# LipSync_Main_Board.net
KiCad netlist of a schematic drawn in EAGLE
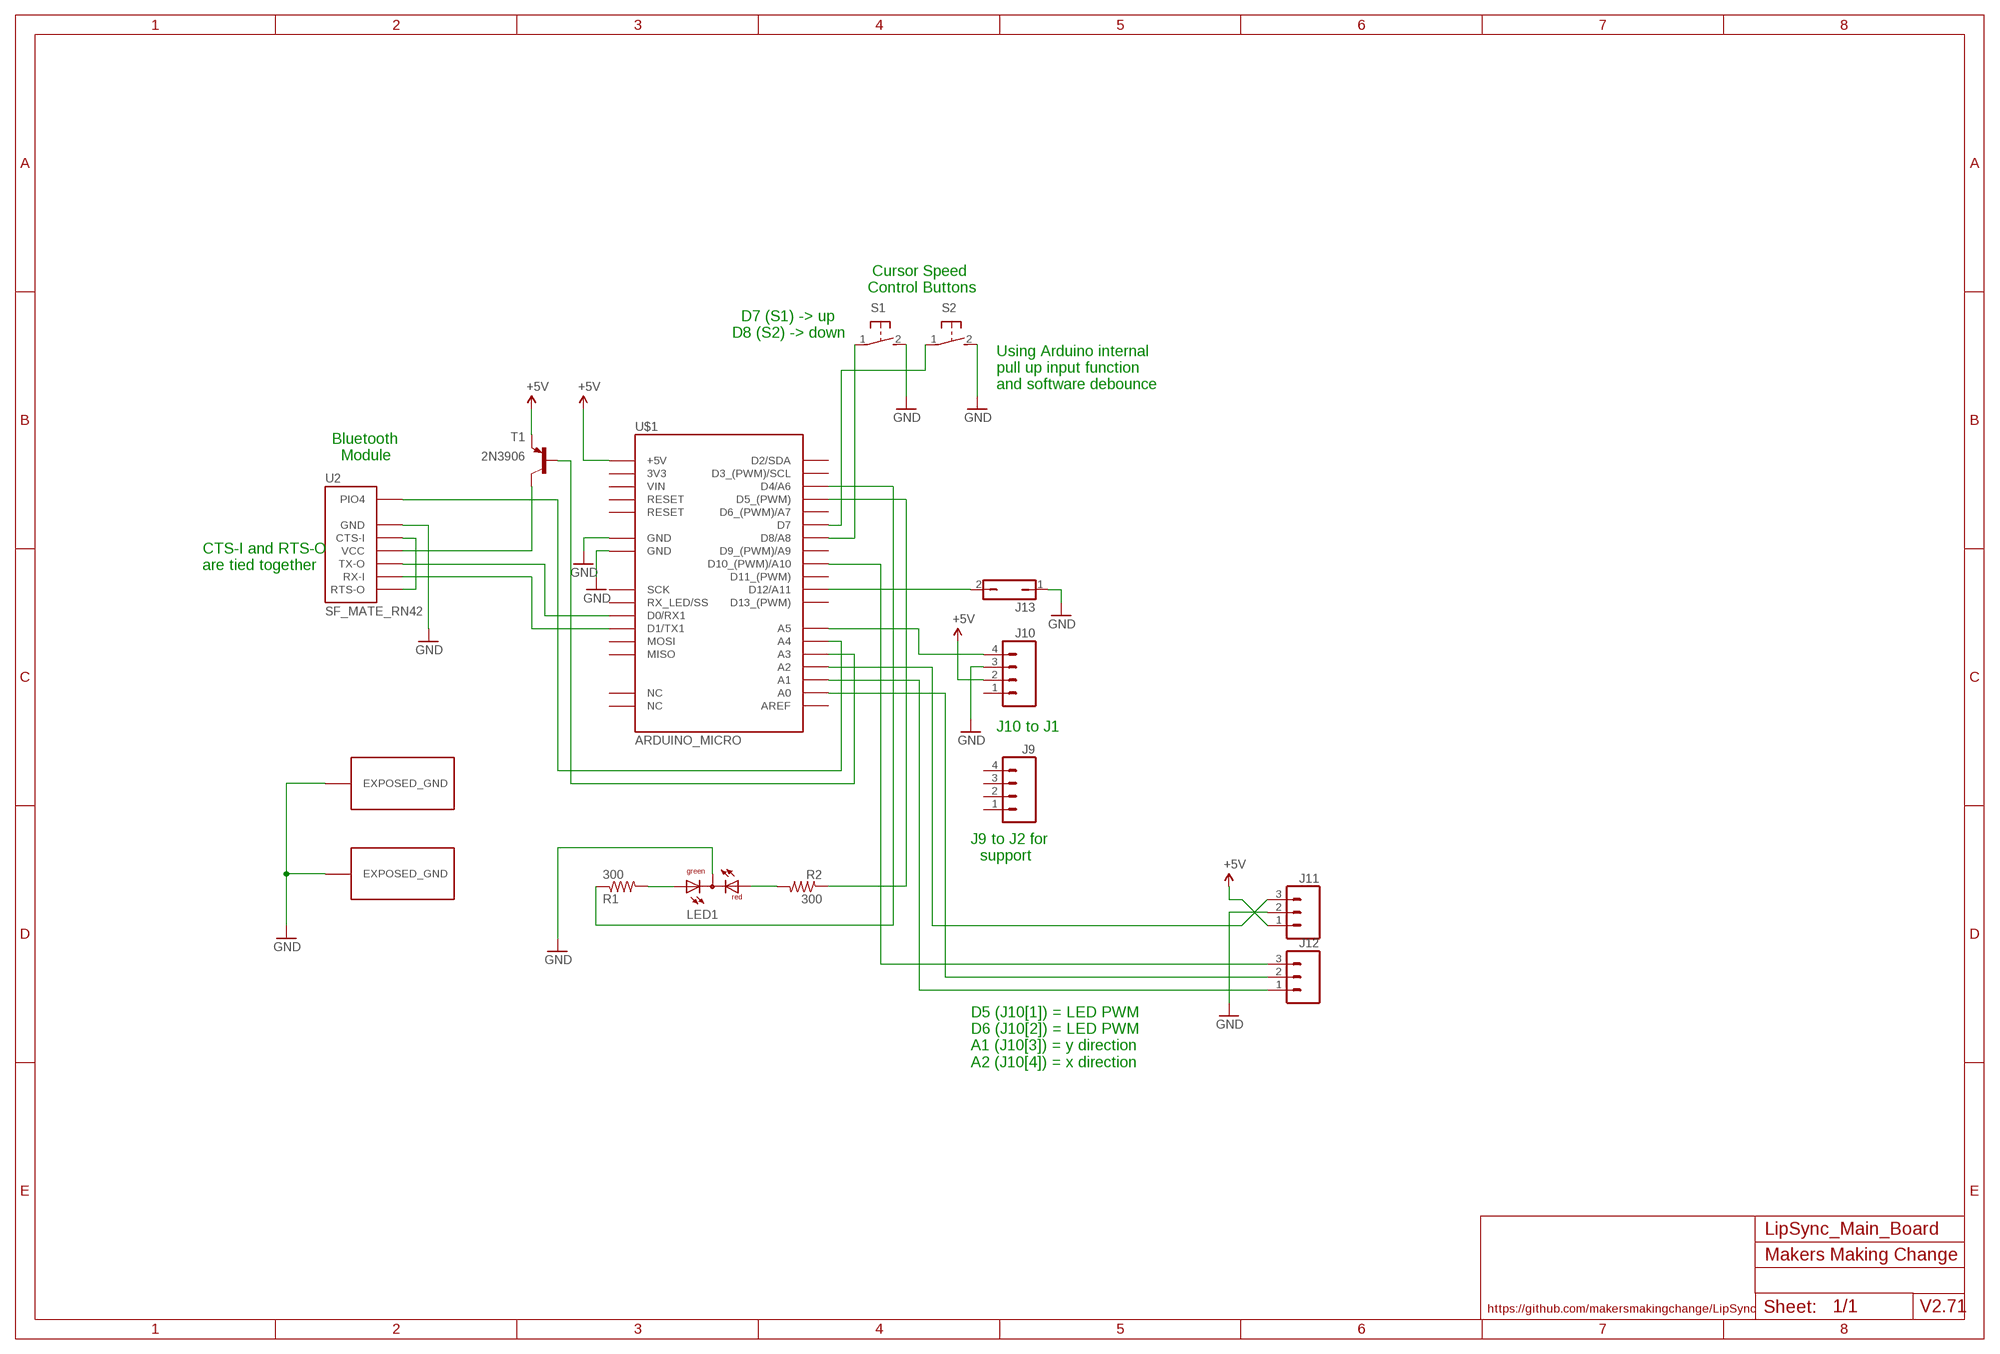
[diagram p0: schematic, sheet 1]

(export (version "E")
  (design (tool "Eeschema 10.0.6"))
  (components
    (comp (ref "J9")
      (value "M04PTH")
      (footprint "eagle-import:1X04")
      (libsource (lib "eagle-import") (part "M04PTH"))
    )
    (comp (ref "J10")
      (value "M04PTH")
      (footprint "eagle-import:1X04")
      (libsource (lib "eagle-import") (part "M04PTH"))
    )
    (comp (ref "J11")
      (value "M03LOCK")
      (footprint "eagle-import:1X03_LOCK")
      (libsource (lib "eagle-import") (part "M03LOCK"))
    )
    (comp (ref "J12")
      (value "M03LOCK")
      (footprint "eagle-import:1X03_LOCK")
      (libsource (lib "eagle-import") (part "M03LOCK"))
    )
    (comp (ref "J13")
      (value "JP1Q")
      (footprint "eagle-import:JP1")
      (libsource (lib "eagle-import") (part "JP1Q"))
    )
    (comp (ref "LED1")
      (value "DUOLED-RG-C")
      (footprint "eagle-import:DUOLED-C-5MM")
      (libsource (lib "eagle-import") (part "DUOLED-RG-C"))
    )
    (comp (ref "R1")
      (value "300")
      (footprint "eagle-import:AXIAL-0.3")
      (libsource (lib "eagle-import") (part "RESISTORAXIAL-0.3"))
    )
    (comp (ref "R2")
      (value "300")
      (footprint "eagle-import:AXIAL-0.3")
      (libsource (lib "eagle-import") (part "RESISTORAXIAL-0.3"))
    )
    (comp (ref "S1")
      (value "31-XXB3F-31XX-CUSTOM")
      (footprint "eagle-import:B3F-31XX-CUSTOM")
      (libsource (lib "eagle-import") (part "31-XXB3F-31XX-CUSTOM"))
    )
    (comp (ref "S2")
      (value "31-XXB3F-31XX-CUSTOM")
      (footprint "eagle-import:B3F-31XX-CUSTOM")
      (libsource (lib "eagle-import") (part "31-XXB3F-31XX-CUSTOM"))
    )
    (comp (ref "T1")
      (value "2N3906")
      (footprint "eagle-import:TO92-EBC")
      (libsource (lib "eagle-import") (part "-PNP-TO92-EBC2N3906"))
    )
    (comp (ref "U$1")
      (value "ARDUINO_MICRO")
      (footprint "eagle-import:ARDUINO_MICRO_HEADER_FOOTPRINT")
      (libsource (lib "eagle-import") (part "ARDUINO_MICRO"))
    )
    (comp (ref "U$2")
      (value "EXPOSED_GND")
      (footprint "eagle-import:EXPOSED_GND")
      (libsource (lib "eagle-import") (part "EXPOSED_GND"))
    )
    (comp (ref "U$3")
      (value "EXPOSED_GND")
      (footprint "eagle-import:EXPOSED_GND")
      (libsource (lib "eagle-import") (part "EXPOSED_GND"))
    )
    (comp (ref "U2")
      (value "SF_MATE_RN42")
      (footprint "eagle-import:BLUE_MATE_RN42_HEADER_FOOTPRINT")
      (libsource (lib "eagle-import") (part "SF_MATE_RN42"))
    )
  )
  (nets
    (net (code "1") (name "+5V") (class "Default")
      (node (ref "J10") (pin "2") (pinfunction "2_2") (pintype "passive"))
      (node (ref "J11") (pin "1") (pinfunction "1_1") (pintype "passive"))
      (node (ref "T1") (pin "E") (pinfunction "E_E") (pintype "passive"))
      (node (ref "U$1") (pin "5V") (pinfunction "+5V_5V") (pintype "power_in"))
    )
    (net (code "2") (name "/3V3") (class "Default")
      (node (ref "U$1") (pin "3V3") (pinfunction "3V3_3V3") (pintype "power_in"))
    )
    (net (code "3") (name "EXPOSED_GND") (class "Default")
      (node (ref "J10") (pin "3") (pinfunction "3_3") (pintype "passive"))
      (node (ref "J11") (pin "2") (pinfunction "2_2") (pintype "passive"))
      (node (ref "J13") (pin "1") (pinfunction "1_1") (pintype "passive"))
      (node (ref "LED1") (pin "C") (pinfunction "C_C") (pintype "passive"))
      (node (ref "S1") (pin "2") (pinfunction "S_2") (pintype "passive"))
      (node (ref "S2") (pin "2") (pinfunction "S_2") (pintype "passive"))
      (node (ref "U$1") (pin "GND") (pinfunction "GND_GND") (pintype "power_in"))
      (node (ref "U$1") (pin "GND@1") (pinfunction "GND_GND@1") (pintype "power_in"))
      (node (ref "U$2") (pin "GND1") (pinfunction "EXPOSED_GND_GND1") (pintype "power_in"))
      (node (ref "U$3") (pin "GND1") (pinfunction "EXPOSED_GND_GND1") (pintype "power_in"))
      (node (ref "U2") (pin "GND") (pinfunction "GND_GND") (pintype "power_in"))
    )
    (net (code "4") (name "Net-(J10-Pad4)") (class "Default")
      (node (ref "J10") (pin "4") (pinfunction "4_4") (pintype "passive"))
      (node (ref "U$1") (pin "A5") (pinfunction "A5_A5") (pintype "bidirectional"))
    )
    (net (code "5") (name "Net-(J11-Pad3)") (class "Default")
      (node (ref "J11") (pin "3") (pinfunction "3_3") (pintype "passive"))
      (node (ref "U$1") (pin "A2") (pinfunction "A2_A2") (pintype "bidirectional"))
    )
    (net (code "6") (name "Net-(J12-Pad1)") (class "Default")
      (node (ref "J12") (pin "1") (pinfunction "1_1") (pintype "passive"))
      (node (ref "U$1") (pin "A1") (pinfunction "A1_A1") (pintype "bidirectional"))
    )
    (net (code "7") (name "Net-(J12-Pad2)") (class "Default")
      (node (ref "J12") (pin "2") (pinfunction "2_2") (pintype "passive"))
      (node (ref "U$1") (pin "A0") (pinfunction "A0_A0") (pintype "bidirectional"))
    )
    (net (code "8") (name "Net-(LED1-AG)") (class "Default")
      (node (ref "LED1") (pin "AX") (pinfunction "AG_AX") (pintype "passive"))
      (node (ref "R1") (pin "P$2") (pinfunction "2_P$2") (pintype "passive"))
    )
    (net (code "9") (name "Net-(R1-1)") (class "Default")
      (node (ref "R1") (pin "P$1") (pinfunction "1_P$1") (pintype "passive"))
      (node (ref "U$1") (pin "D4") (pinfunction "D4/A6_D4") (pintype "bidirectional"))
    )
    (net (code "10") (name "Net-(R2-1)") (class "Default")
      (node (ref "R2") (pin "P$1") (pinfunction "1_P$1") (pintype "passive"))
      (node (ref "U$1") (pin "D5") (pinfunction "D5_(PWM)_D5") (pintype "bidirectional"))
    )
    (net (code "11") (name "Net-(R2-2)") (class "Default")
      (node (ref "LED1") (pin "AR") (pinfunction "AR_AR") (pintype "passive"))
      (node (ref "R2") (pin "P$2") (pinfunction "2_P$2") (pintype "passive"))
    )
    (net (code "12") (name "Net-(S1-P)") (class "Default")
      (node (ref "S1") (pin "1") (pinfunction "P_1") (pintype "passive"))
      (node (ref "U$1") (pin "D8") (pinfunction "D8/A8_D8") (pintype "bidirectional"))
    )
    (net (code "13") (name "Net-(S2-P)") (class "Default")
      (node (ref "S2") (pin "1") (pinfunction "P_1") (pintype "passive"))
      (node (ref "U$1") (pin "D7") (pinfunction "D7_D7") (pintype "bidirectional"))
    )
    (net (code "14") (name "Net-(T1-PadB)") (class "Default")
      (node (ref "T1") (pin "B") (pinfunction "B_B") (pintype "passive"))
      (node (ref "U$1") (pin "A3") (pinfunction "A3_A3") (pintype "bidirectional"))
    )
    (net (code "15") (name "Net-(T1-PadC)") (class "Default")
      (node (ref "T1") (pin "C") (pinfunction "C_C") (pintype "passive"))
      (node (ref "U2") (pin "VCC") (pinfunction "VCC_VCC") (pintype "power_in"))
    )
    (net (code "16") (name "Net-(U$1-D0{slash}RX1)") (class "Default")
      (node (ref "U$1") (pin "RX1") (pinfunction "D0/RX1_RX1") (pintype "input"))
      (node (ref "U2") (pin "TX-O") (pinfunction "TX-O_TX-O") (pintype "output"))
    )
    (net (code "17") (name "Net-(U$1-D1{slash}TX1)") (class "Default")
      (node (ref "U$1") (pin "TX1") (pinfunction "D1/TX1_TX1") (pintype "output"))
      (node (ref "U2") (pin "RX-I") (pinfunction "RX-I_RX-I") (pintype "input"))
    )
    (net (code "18") (name "Net-(U$1-D10_(PWM){slash}A10)") (class "Default")
      (node (ref "J12") (pin "3") (pinfunction "3_3") (pintype "passive"))
      (node (ref "U$1") (pin "D10") (pinfunction "D10_(PWM)/A10_D10") (pintype "bidirectional"))
    )
    (net (code "19") (name "Net-(U$1-D12{slash}A11)") (class "Default")
      (node (ref "J13") (pin "2") (pinfunction "2_2") (pintype "passive"))
      (node (ref "U$1") (pin "D12") (pinfunction "D12/A11_D12") (pintype "bidirectional"))
    )
    (net (code "20") (name "Net-(U$1-PadA4)") (class "Default")
      (node (ref "U$1") (pin "A4") (pinfunction "A4_A4") (pintype "bidirectional"))
      (node (ref "U2") (pin "PIO4") (pinfunction "PIO4_PIO4") (pintype "input"))
    )
    (net (code "21") (name "Net-(U2-PadCTS-I)") (class "Default")
      (node (ref "U2") (pin "CTS-I") (pinfunction "CTS-I_CTS-I") (pintype "input"))
      (node (ref "U2") (pin "RTS-O") (pinfunction "RTS-O_RTS-O") (pintype "output"))
    )
    (net (code "22") (name "unconnected-(J9-Pad1)") (class "Default")
      (node (ref "J9") (pin "1") (pinfunction "1_1") (pintype "passive"))
    )
    (net (code "23") (name "unconnected-(J9-Pad2)") (class "Default")
      (node (ref "J9") (pin "2") (pinfunction "2_2") (pintype "passive"))
    )
    (net (code "24") (name "unconnected-(J9-Pad3)") (class "Default")
      (node (ref "J9") (pin "3") (pinfunction "3_3") (pintype "passive"))
    )
    (net (code "25") (name "unconnected-(J9-Pad4)") (class "Default")
      (node (ref "J9") (pin "4") (pinfunction "4_4") (pintype "passive"))
    )
    (net (code "26") (name "unconnected-(J10-Pad1)") (class "Default")
      (node (ref "J10") (pin "1") (pinfunction "1_1") (pintype "passive"))
    )
    (net (code "27") (name "unconnected-(U$1-AREF-PadREF)") (class "Default")
      (node (ref "U$1") (pin "REF") (pinfunction "AREF_REF") (pintype "input"))
    )
    (net (code "28") (name "unconnected-(U$1-D2{slash}SDA-PadD2)") (class "Default")
      (node (ref "U$1") (pin "D2") (pinfunction "D2/SDA_D2") (pintype "bidirectional"))
    )
    (net (code "29") (name "unconnected-(U$1-D3_(PWM){slash}SCL-PadD3)") (class "Default")
      (node (ref "U$1") (pin "D3") (pinfunction "D3_(PWM)/SCL_D3") (pintype "bidirectional"))
    )
    (net (code "30") (name "unconnected-(U$1-D6_(PWM){slash}A7-PadD6)") (class "Default")
      (node (ref "U$1") (pin "D6") (pinfunction "D6_(PWM)/A7_D6") (pintype "bidirectional"))
    )
    (net (code "31") (name "unconnected-(U$1-D9_(PWM){slash}A9-PadD9)") (class "Default")
      (node (ref "U$1") (pin "D9") (pinfunction "D9_(PWM)/A9_D9") (pintype "bidirectional"))
    )
    (net (code "32") (name "unconnected-(U$1-D11_(PWM)-PadD11)") (class "Default")
      (node (ref "U$1") (pin "D11") (pinfunction "D11_(PWM)_D11") (pintype "bidirectional"))
    )
    (net (code "33") (name "unconnected-(U$1-D13_(PWM)-PadD13)") (class "Default")
      (node (ref "U$1") (pin "D13") (pinfunction "D13_(PWM)_D13") (pintype "bidirectional"))
    )
    (net (code "34") (name "unconnected-(U$1-NC-PadNC@1)") (class "Default")
      (node (ref "U$1") (pin "NC@1") (pinfunction "NC_NC@1") (pintype "no_connect"))
    )
    (net (code "35") (name "unconnected-(U$1-PadMISO)") (class "Default")
      (node (ref "U$1") (pin "MISO") (pinfunction "MISO_MISO") (pintype "bidirectional"))
    )
    (net (code "36") (name "unconnected-(U$1-PadMOSI)") (class "Default")
      (node (ref "U$1") (pin "MOSI") (pinfunction "MOSI_MOSI") (pintype "bidirectional"))
    )
    (net (code "37") (name "unconnected-(U$1-PadNC)") (class "Default")
      (node (ref "U$1") (pin "NC") (pinfunction "NC_NC") (pintype "no_connect"))
    )
    (net (code "38") (name "unconnected-(U$1-PadSCK)") (class "Default")
      (node (ref "U$1") (pin "SCK") (pinfunction "SCK_SCK") (pintype "output"))
    )
    (net (code "39") (name "unconnected-(U$1-PadVIN)") (class "Default")
      (node (ref "U$1") (pin "VIN") (pinfunction "VIN_VIN") (pintype "input"))
    )
    (net (code "40") (name "unconnected-(U$1-RESET-PadRST)") (class "Default")
      (node (ref "U$1") (pin "RST") (pinfunction "RESET_RST") (pintype "input"))
    )
    (net (code "41") (name "unconnected-(U$1-RESET-PadRST@1)") (class "Default")
      (node (ref "U$1") (pin "RST@1") (pinfunction "RESET_RST@1") (pintype "input"))
    )
    (net (code "42") (name "unconnected-(U$1-RX_LED{slash}SS-PadSS)") (class "Default")
      (node (ref "U$1") (pin "SS") (pinfunction "RX_LED/SS_SS") (pintype "bidirectional"))
    )
  )
)
